# V1_0.net
KiCad netlist of a schematic drawn in Altium Designer
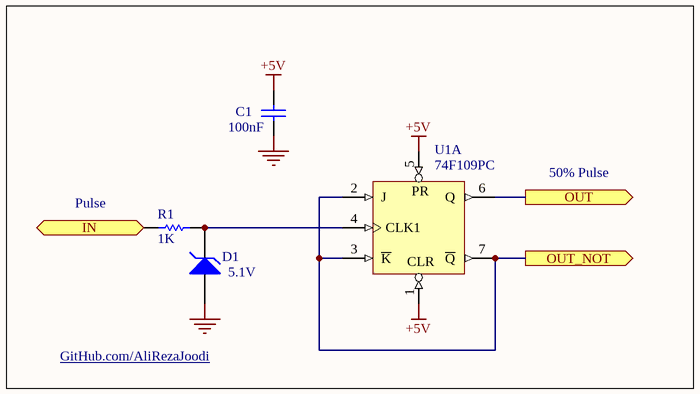
[diagram p0: V1.0.SchDoc]

(export (version "E")
  (design (tool "Eeschema 10.0.6"))
  (components
    (comp (ref "C1")
      (value "100nF")
      (footprint "CAPNTO2.54-3.05x1.78A")
      (description "Capacitor")
      (fields (field (name "MANUFACTURER") "Generic Components") (field (name "PUBLISHER") "Altium Limited"))
      (libsource (lib "Miscellaneous Devices") (part "Cap"))
    )
    (comp (ref "D1")
      (value "5.1V")
      (footprint "DIODE0.4_Glass")
      (description "Zener Diode")
      (fields (field (name "MANUFACTURER") "Generic Components") (field (name "PUBLISHER") "Altium Limited"))
      (libsource (lib "Miscellaneous Devices") (part "D Zener"))
    )
    (comp (ref "R1")
      (value "1K")
      (footprint "AXIAL-0.4")
      (description "Resistor")
      (fields (field (name "PUBLISHER") "Altium Limited"))
      (libsource (lib "Miscellaneous Devices") (part "Res1"))
    )
    (comp (ref "U1")
      (value "74F109PC")
      (footprint "N16E")
      (description "Dual J-K Positive Edge-Triggered Flip-Flop")
      (fields (field (name "PUBLISHER") "Altium Limited"))
      (libsource (lib "FSC Logic Flip-Flop") (part "74F109PC"))
    )
  )
  (nets
    (net (code "1") (name "+5V") (class "Default")
      (node (ref "C1") (pin "2") (pinfunction "2_2") (pintype "passive"))
      (node (ref "U1") (pin "1") (pinfunction "CLR_1") (pintype "input"))
      (node (ref "U1") (pin "5") (pinfunction "PR_5") (pintype "input"))
    )
    (net (code "2") (name "/IN") (class "Default")
      (node (ref "R1") (pin "2") (pinfunction "2_2") (pintype "passive"))
    )
    (net (code "3") (name "/OUT") (class "Default")
      (node (ref "U1") (pin "6") (pinfunction "Q_6") (pintype "output"))
    )
    (net (code "4") (name "/OUT_NOT") (class "Default")
      (node (ref "U1") (pin "2") (pinfunction "J_2") (pintype "input"))
      (node (ref "U1") (pin "3") (pinfunction "~{K}_3") (pintype "input"))
      (node (ref "U1") (pin "7") (pinfunction "~{Q}_7") (pintype "output"))
    )
    (net (code "5") (name "GND") (class "Default")
      (node (ref "C1") (pin "1") (pinfunction "1_1") (pintype "passive"))
      (node (ref "D1") (pin "1") (pinfunction "A_1") (pintype "passive"))
      (node (ref "U1") (pin "8") (pinfunction "GND_8") (pintype "power_in"))
    )
    (net (code "6") (name "Net-(D1-K)") (class "Default")
      (node (ref "D1") (pin "2") (pinfunction "K_2") (pintype "passive"))
      (node (ref "R1") (pin "1") (pinfunction "1_1") (pintype "passive"))
      (node (ref "U1") (pin "4") (pinfunction "CLK1_4") (pintype "input"))
    )
    (net (code "7") (name "VCC") (class "Default")
      (node (ref "U1") (pin "16") (pinfunction "VCC_16") (pintype "power_in"))
    )
  )
)
